# thermostatMechanicalSingleStage.net
KiCad netlist of a schematic drawn in EAGLE
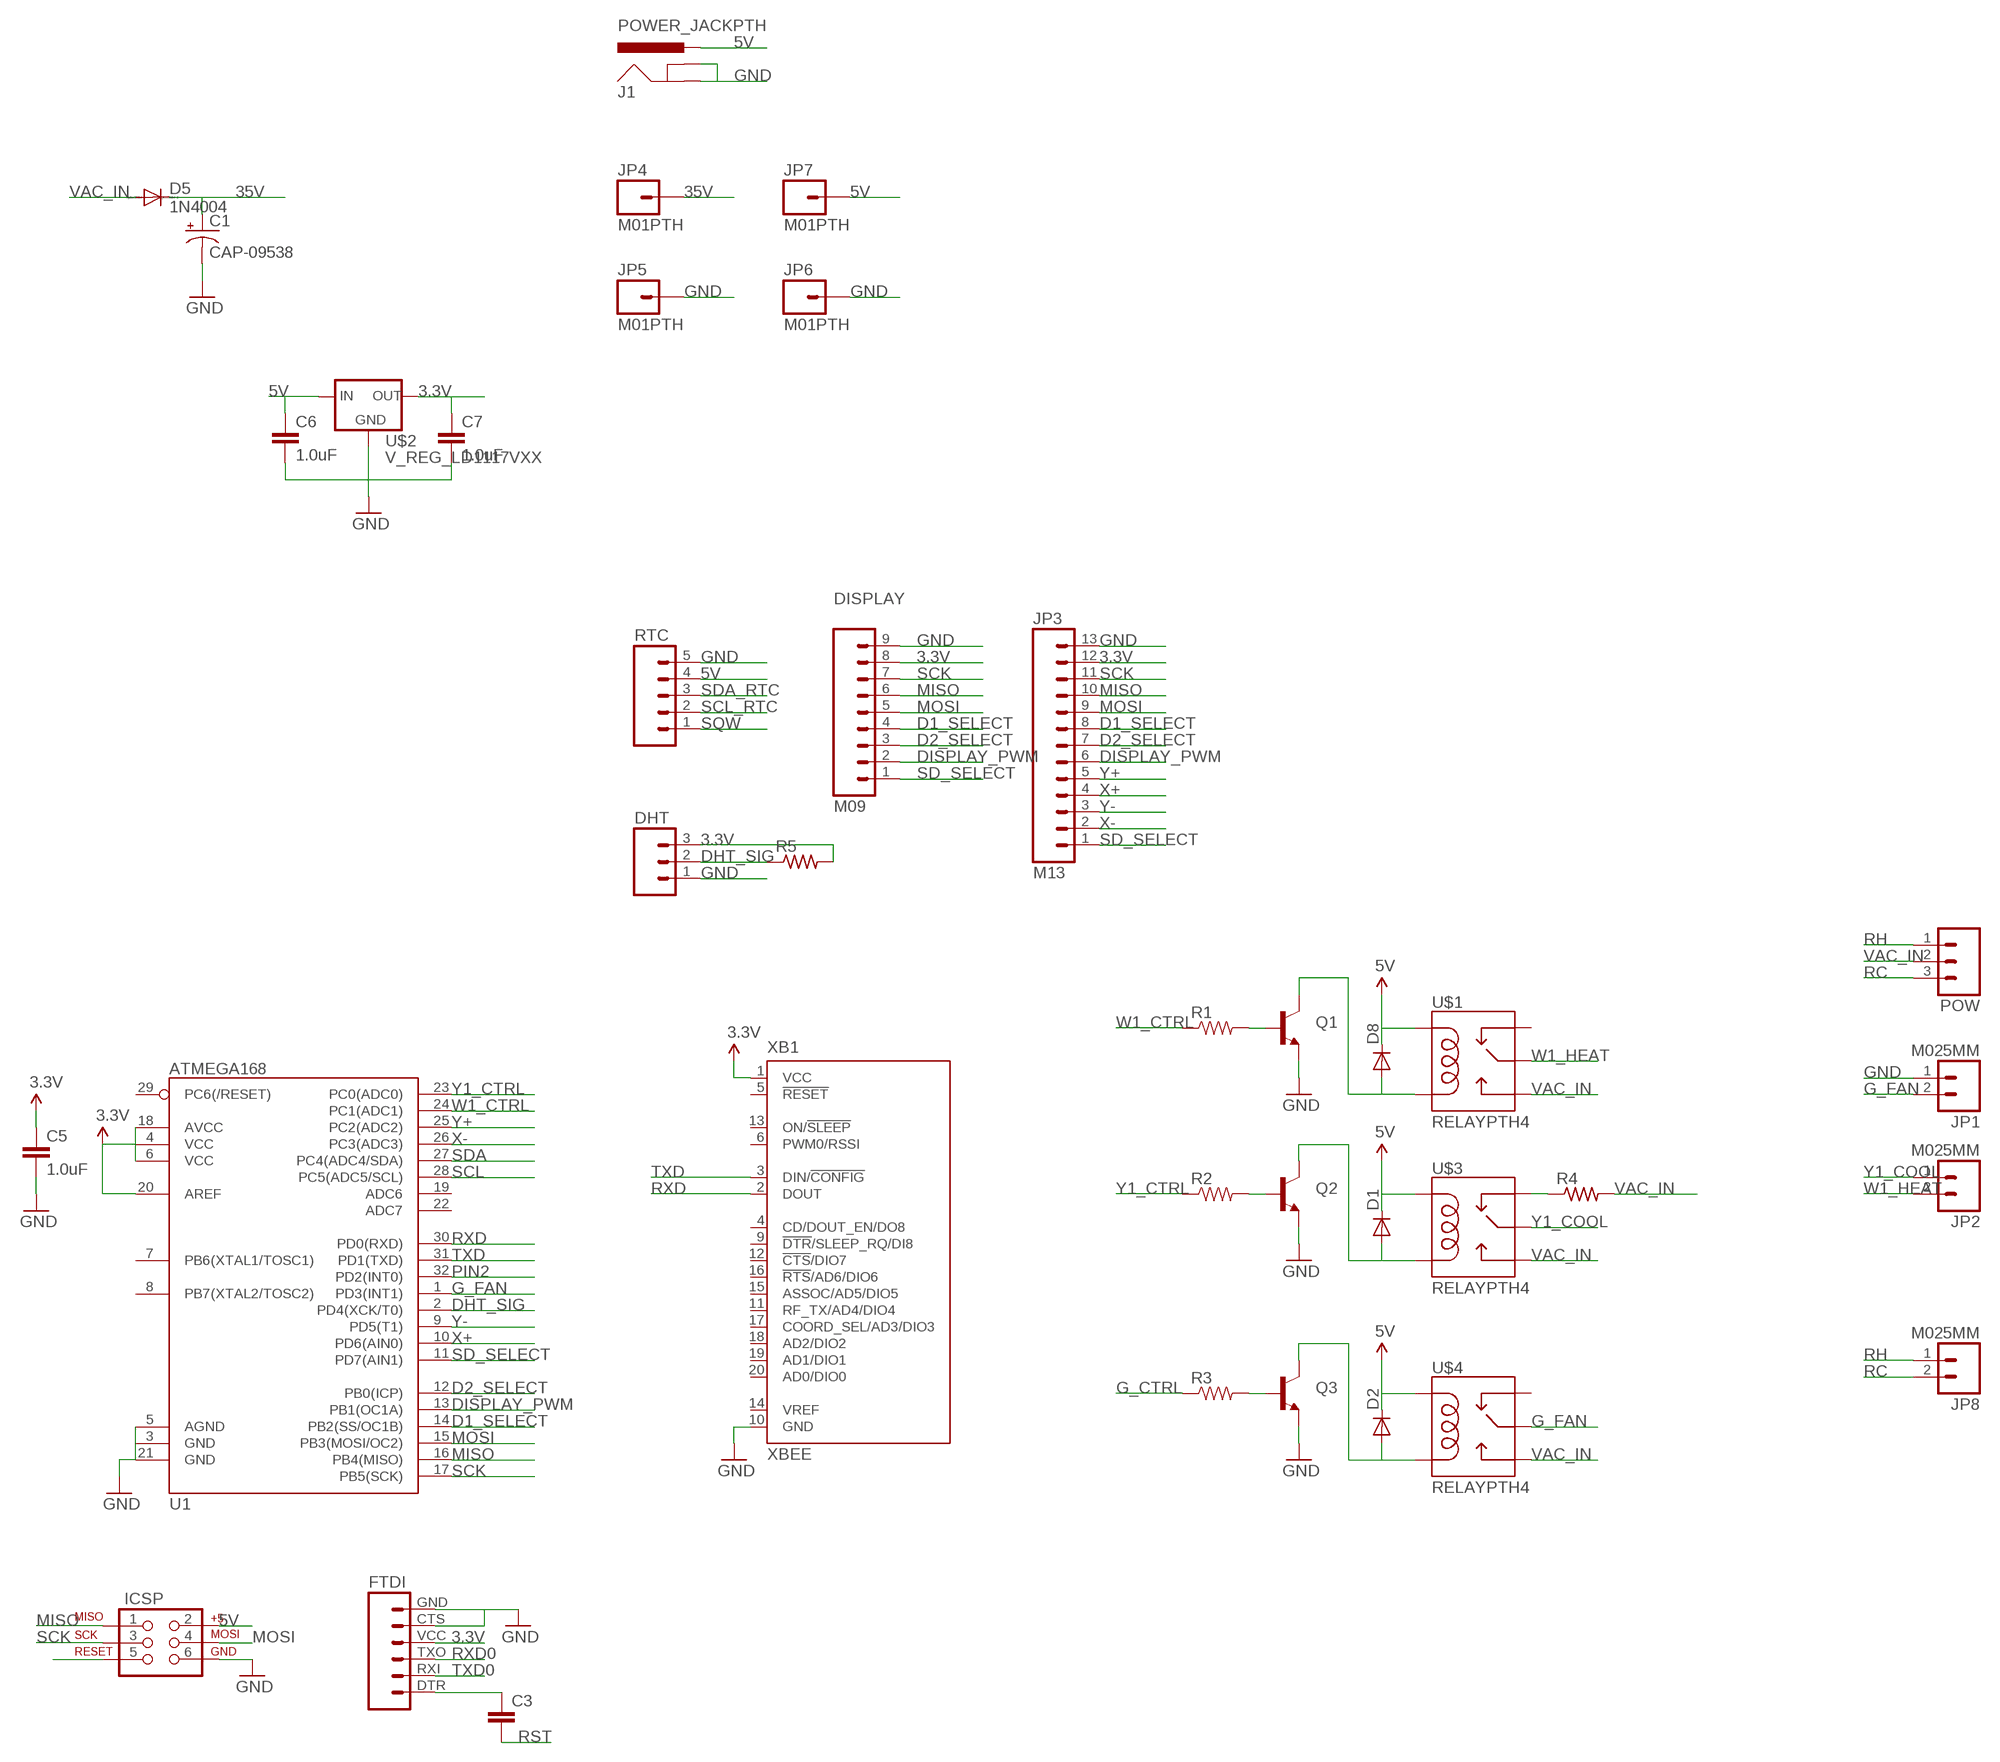
[diagram p0: schematic, sheet 1]

(export (version "E")
  (design (tool "Eeschema 10.0.6"))
  (components
    (comp (ref "C1")
      (value "CAP-09538")
      (footprint "eagle-import:CPOL-RADIAL-1000UF-25V")
      (libsource (lib "eagle-import") (part "1000UF-25V(PTH)"))
    )
    (comp (ref "C3")
      (value "CAP1206")
      (footprint "eagle-import:1206")
      (libsource (lib "eagle-import") (part "CAP1206"))
    )
    (comp (ref "C5")
      (value "1.0uF")
      (footprint "eagle-import:1206")
      (libsource (lib "eagle-import") (part "1.0UF50V10%(1206)"))
    )
    (comp (ref "C6")
      (value "1.0uF")
      (footprint "eagle-import:1206")
      (libsource (lib "eagle-import") (part "1.0UF50V10%(1206)"))
    )
    (comp (ref "C7")
      (value "1.0uF")
      (footprint "eagle-import:1206")
      (libsource (lib "eagle-import") (part "1.0UF50V10%(1206)"))
    )
    (comp (ref "D1")
      (value "DIODE1N4148")
      (footprint "eagle-import:DIODE-1N4148")
      (libsource (lib "eagle-import") (part "DIODE1N4148"))
    )
    (comp (ref "D2")
      (value "DIODE1N4148")
      (footprint "eagle-import:DIODE-1N4148")
      (libsource (lib "eagle-import") (part "DIODE1N4148"))
    )
    (comp (ref "D5")
      (value "1N4004")
      (footprint "eagle-import:DO41-10")
      (libsource (lib "eagle-import") (part "1N4004"))
    )
    (comp (ref "D8")
      (value "DIODE1N4148")
      (footprint "eagle-import:DIODE-1N4148")
      (libsource (lib "eagle-import") (part "DIODE1N4148"))
    )
    (comp (ref "DHT")
      (value "M03PTH")
      (footprint "eagle-import:1X03")
      (libsource (lib "eagle-import") (part "M03PTH"))
    )
    (comp (ref "DISPLAY")
      (value "M09")
      (footprint "eagle-import:1X09")
      (libsource (lib "eagle-import") (part "M09"))
    )
    (comp (ref "FTDI")
      (value "FTDI_BASICPTH")
      (footprint "eagle-import:FTDI_BASIC")
      (libsource (lib "eagle-import") (part "FTDI_BASICPTH"))
    )
    (comp (ref "ICSP")
      (value "AVR_SPI_PRG_6NS")
      (footprint "eagle-import:2X3-NS")
      (libsource (lib "eagle-import") (part "AVR_SPI_PRG_6NS"))
    )
    (comp (ref "J1")
      (value "POWER_JACKPTH")
      (footprint "eagle-import:POWER_JACK_PTH")
      (libsource (lib "eagle-import") (part "POWER_JACKPTH"))
    )
    (comp (ref "JP1")
      (value "M025MM")
      (footprint "eagle-import:SCREWTERMINAL-5MM-2")
      (libsource (lib "eagle-import") (part "M025MM"))
    )
    (comp (ref "JP2")
      (value "M025MM")
      (footprint "eagle-import:SCREWTERMINAL-5MM-2")
      (libsource (lib "eagle-import") (part "M025MM"))
    )
    (comp (ref "JP3")
      (value "M13")
      (footprint "eagle-import:1X13")
      (libsource (lib "eagle-import") (part "M13"))
    )
    (comp (ref "JP4")
      (value "M01PTH")
      (footprint "eagle-import:1X01")
      (libsource (lib "eagle-import") (part "M01PTH"))
    )
    (comp (ref "JP5")
      (value "M01PTH")
      (footprint "eagle-import:1X01")
      (libsource (lib "eagle-import") (part "M01PTH"))
    )
    (comp (ref "JP6")
      (value "M01PTH")
      (footprint "eagle-import:1X01")
      (libsource (lib "eagle-import") (part "M01PTH"))
    )
    (comp (ref "JP7")
      (value "M01PTH")
      (footprint "eagle-import:1X01")
      (libsource (lib "eagle-import") (part "M01PTH"))
    )
    (comp (ref "JP8")
      (value "M025MM")
      (footprint "eagle-import:SCREWTERMINAL-5MM-2")
      (libsource (lib "eagle-import") (part "M025MM"))
    )
    (comp (ref "POW")
      (value "M03PTH")
      (footprint "eagle-import:1X03")
      (libsource (lib "eagle-import") (part "M03PTH"))
    )
    (comp (ref "Q1")
      (value "TRANSISTOR_NPNSOT23")
      (footprint "eagle-import:SOT23")
      (libsource (lib "eagle-import") (part "TRANSISTOR_NPNSOT23"))
    )
    (comp (ref "Q2")
      (value "TRANSISTOR_NPNSOT23")
      (footprint "eagle-import:SOT23")
      (libsource (lib "eagle-import") (part "TRANSISTOR_NPNSOT23"))
    )
    (comp (ref "Q3")
      (value "TRANSISTOR_NPNSOT23")
      (footprint "eagle-import:SOT23")
      (libsource (lib "eagle-import") (part "TRANSISTOR_NPNSOT23"))
    )
    (comp (ref "R1")
      (value "RESISTOR1206")
      (footprint "eagle-import:1206")
      (libsource (lib "eagle-import") (part "RESISTOR1206"))
    )
    (comp (ref "R2")
      (value "RESISTOR1206")
      (footprint "eagle-import:1206")
      (libsource (lib "eagle-import") (part "RESISTOR1206"))
    )
    (comp (ref "R3")
      (value "RESISTOR1206")
      (footprint "eagle-import:1206")
      (libsource (lib "eagle-import") (part "RESISTOR1206"))
    )
    (comp (ref "R4")
      (value "R-US_0204/7")
      (footprint "eagle-import:0204_7")
      (libsource (lib "eagle-import") (part "rcl_R-US_0204/7"))
    )
    (comp (ref "R5")
      (value "R-US_M1206")
      (footprint "eagle-import:M1206")
      (libsource (lib "eagle-import") (part "R-US_M1206"))
    )
    (comp (ref "RTC")
      (value "M05PTH")
      (footprint "eagle-import:1X05")
      (libsource (lib "eagle-import") (part "M05PTH"))
    )
    (comp (ref "U$1")
      (value "RELAYPTH4")
      (footprint "eagle-import:RELAY-JZC")
      (libsource (lib "eagle-import") (part "RELAYPTH4"))
    )
    (comp (ref "U$2")
      (value "V_REG_LD1117VXX")
      (footprint "eagle-import:78XXL")
      (libsource (lib "eagle-import") (part "V_REG_LD1117VXX"))
    )
    (comp (ref "U$3")
      (value "RELAYPTH4")
      (footprint "eagle-import:RELAY-JZC")
      (libsource (lib "eagle-import") (part "RELAYPTH4"))
    )
    (comp (ref "U$4")
      (value "RELAYPTH4")
      (footprint "eagle-import:RELAY-JZC")
      (libsource (lib "eagle-import") (part "RELAYPTH4"))
    )
    (comp (ref "U1")
      (value "ATMEGA168")
      (footprint "eagle-import:TQFP32-08")
      (libsource (lib "eagle-import") (part "ATMEGA168"))
    )
    (comp (ref "XB1")
      (value "XBEE")
      (footprint "eagle-import:XBEE")
      (fields (field (name "MPN") "XBP24-Z7UIT-004"))
      (libsource (lib "eagle-import") (part "XBEE"))
    )
  )
  (nets
    (net (code "1") (name "/35V") (class "Default")
      (node (ref "C1") (pin "+") (pinfunction "+_+") (pintype "passive"))
      (node (ref "D5") (pin "C") (pinfunction "C_C") (pintype "passive"))
      (node (ref "JP4") (pin "1") (pinfunction "1_1") (pintype "passive"))
    )
    (net (code "2") (name "/D1_SELECT") (class "Default")
      (node (ref "DISPLAY") (pin "4") (pinfunction "4_4") (pintype "passive"))
      (node (ref "JP3") (pin "8") (pinfunction "8_8") (pintype "passive"))
      (node (ref "U1") (pin "14") (pinfunction "PB2(SS/OC1B)_14") (pintype "bidirectional"))
    )
    (net (code "3") (name "/D2_SELECT") (class "Default")
      (node (ref "DISPLAY") (pin "3") (pinfunction "3_3") (pintype "passive"))
      (node (ref "JP3") (pin "7") (pinfunction "7_7") (pintype "passive"))
      (node (ref "U1") (pin "12") (pinfunction "PB0(ICP)_12") (pintype "bidirectional"))
    )
    (net (code "4") (name "/DHT_SIG") (class "Default")
      (node (ref "DHT") (pin "2") (pinfunction "2_2") (pintype "passive"))
      (node (ref "R5") (pin "1") (pinfunction "1_1") (pintype "passive"))
      (node (ref "U1") (pin "2") (pinfunction "PD4(XCK/T0)_2") (pintype "bidirectional"))
    )
    (net (code "5") (name "/DISPLAY_PWM") (class "Default")
      (node (ref "DISPLAY") (pin "2") (pinfunction "2_2") (pintype "passive"))
      (node (ref "JP3") (pin "6") (pinfunction "6_6") (pintype "passive"))
      (node (ref "U1") (pin "13") (pinfunction "PB1(OC1A)_13") (pintype "bidirectional"))
    )
    (net (code "6") (name "/G_CTRL") (class "Default")
      (node (ref "R3") (pin "1") (pinfunction "1_1") (pintype "passive"))
    )
    (net (code "7") (name "/G_FAN") (class "Default")
      (node (ref "JP1") (pin "2") (pinfunction "2_2") (pintype "passive"))
      (node (ref "U$4") (pin "4") (pinfunction "MAIN_4") (pintype "bidirectional"))
      (node (ref "U1") (pin "1") (pinfunction "PD3(INT1)_1") (pintype "bidirectional"))
    )
    (net (code "8") (name "/MISO") (class "Default")
      (node (ref "DISPLAY") (pin "6") (pinfunction "6_6") (pintype "passive"))
      (node (ref "ICSP") (pin "1") (pinfunction "1_1") (pintype "passive"))
      (node (ref "JP3") (pin "10") (pinfunction "10_10") (pintype "passive"))
      (node (ref "U1") (pin "16") (pinfunction "PB4(MISO)_16") (pintype "bidirectional"))
    )
    (net (code "9") (name "/MOSI") (class "Default")
      (node (ref "DISPLAY") (pin "5") (pinfunction "5_5") (pintype "passive"))
      (node (ref "ICSP") (pin "4") (pinfunction "4_4") (pintype "passive"))
      (node (ref "JP3") (pin "9") (pinfunction "9_9") (pintype "passive"))
      (node (ref "U1") (pin "15") (pinfunction "PB3(MOSI/OC2)_15") (pintype "bidirectional"))
    )
    (net (code "10") (name "/PIN2") (class "Default")
      (node (ref "U1") (pin "32") (pinfunction "PD2(INT0)_32") (pintype "bidirectional"))
    )
    (net (code "11") (name "/RC") (class "Default")
      (node (ref "JP8") (pin "2") (pinfunction "2_2") (pintype "passive"))
      (node (ref "POW") (pin "3") (pinfunction "3_3") (pintype "passive"))
    )
    (net (code "12") (name "/RH") (class "Default")
      (node (ref "JP8") (pin "1") (pinfunction "1_1") (pintype "passive"))
      (node (ref "POW") (pin "1") (pinfunction "1_1") (pintype "passive"))
    )
    (net (code "13") (name "/RST") (class "Default")
      (node (ref "C3") (pin "2") (pinfunction "2_2") (pintype "passive"))
      (node (ref "ICSP") (pin "5") (pinfunction "5_5") (pintype "passive"))
    )
    (net (code "14") (name "/RXD") (class "Default")
      (node (ref "U1") (pin "30") (pinfunction "PD0(RXD)_30") (pintype "bidirectional"))
      (node (ref "XB1") (pin "2") (pinfunction "DOUT_2") (pintype "output"))
    )
    (net (code "15") (name "/RXD0") (class "Default")
      (node (ref "FTDI") (pin "TXO") (pinfunction "3_TXO") (pintype "passive"))
    )
    (net (code "16") (name "/SCK") (class "Default")
      (node (ref "DISPLAY") (pin "7") (pinfunction "7_7") (pintype "passive"))
      (node (ref "ICSP") (pin "3") (pinfunction "3_3") (pintype "passive"))
      (node (ref "JP3") (pin "11") (pinfunction "11_11") (pintype "passive"))
      (node (ref "U1") (pin "17") (pinfunction "PB5(SCK)_17") (pintype "bidirectional"))
    )
    (net (code "17") (name "/SCL") (class "Default")
      (node (ref "U1") (pin "28") (pinfunction "PC5(ADC5/SCL)_28") (pintype "bidirectional"))
    )
    (net (code "18") (name "/SCL_RTC") (class "Default")
      (node (ref "RTC") (pin "2") (pinfunction "2_2") (pintype "passive"))
    )
    (net (code "19") (name "/SDA") (class "Default")
      (node (ref "U1") (pin "27") (pinfunction "PC4(ADC4/SDA)_27") (pintype "bidirectional"))
    )
    (net (code "20") (name "/SDA_RTC") (class "Default")
      (node (ref "RTC") (pin "3") (pinfunction "3_3") (pintype "passive"))
    )
    (net (code "21") (name "/SD_SELECT") (class "Default")
      (node (ref "DISPLAY") (pin "1") (pinfunction "1_1") (pintype "passive"))
      (node (ref "JP3") (pin "1") (pinfunction "1_1") (pintype "passive"))
      (node (ref "U1") (pin "11") (pinfunction "PD7(AIN1)_11") (pintype "bidirectional"))
    )
    (net (code "22") (name "/SQW") (class "Default")
      (node (ref "RTC") (pin "1") (pinfunction "1_1") (pintype "passive"))
    )
    (net (code "23") (name "/TXD") (class "Default")
      (node (ref "U1") (pin "31") (pinfunction "PD1(TXD)_31") (pintype "bidirectional"))
      (node (ref "XB1") (pin "3") (pinfunction "DIN/~{CONFIG}_3") (pintype "input"))
    )
    (net (code "24") (name "/TXD0") (class "Default")
      (node (ref "FTDI") (pin "RXI") (pinfunction "2_RXI") (pintype "passive"))
    )
    (net (code "25") (name "/VAC_IN") (class "Default")
      (node (ref "D5") (pin "A") (pinfunction "A_A") (pintype "passive"))
      (node (ref "POW") (pin "2") (pinfunction "2_2") (pintype "passive"))
      (node (ref "R4") (pin "2") (pinfunction "2_2") (pintype "passive"))
      (node (ref "U$1") (pin "3") (pinfunction "NO_3") (pintype "bidirectional"))
      (node (ref "U$3") (pin "3") (pinfunction "NO_3") (pintype "bidirectional"))
      (node (ref "U$4") (pin "3") (pinfunction "NO_3") (pintype "bidirectional"))
    )
    (net (code "26") (name "/W1_CTRL") (class "Default")
      (node (ref "R1") (pin "1") (pinfunction "1_1") (pintype "passive"))
      (node (ref "U1") (pin "24") (pinfunction "PC1(ADC1)_24") (pintype "bidirectional"))
    )
    (net (code "27") (name "/W1_HEAT") (class "Default")
      (node (ref "JP2") (pin "2") (pinfunction "2_2") (pintype "passive"))
      (node (ref "U$1") (pin "4") (pinfunction "MAIN_4") (pintype "bidirectional"))
    )
    (net (code "28") (name "/X+") (class "Default")
      (node (ref "JP3") (pin "4") (pinfunction "4_4") (pintype "passive"))
      (node (ref "U1") (pin "10") (pinfunction "PD6(AIN0)_10") (pintype "bidirectional"))
    )
    (net (code "29") (name "/X-") (class "Default")
      (node (ref "JP3") (pin "2") (pinfunction "2_2") (pintype "passive"))
      (node (ref "U1") (pin "26") (pinfunction "PC3(ADC3)_26") (pintype "bidirectional"))
    )
    (net (code "30") (name "/Y+") (class "Default")
      (node (ref "JP3") (pin "5") (pinfunction "5_5") (pintype "passive"))
      (node (ref "U1") (pin "25") (pinfunction "PC2(ADC2)_25") (pintype "bidirectional"))
    )
    (net (code "31") (name "/Y-") (class "Default")
      (node (ref "JP3") (pin "3") (pinfunction "3_3") (pintype "passive"))
      (node (ref "U1") (pin "9") (pinfunction "PD5(T1)_9") (pintype "bidirectional"))
    )
    (net (code "32") (name "/Y1_COOL") (class "Default")
      (node (ref "JP2") (pin "1") (pinfunction "1_1") (pintype "passive"))
      (node (ref "U$3") (pin "4") (pinfunction "MAIN_4") (pintype "bidirectional"))
    )
    (net (code "33") (name "/Y1_CTRL") (class "Default")
      (node (ref "R2") (pin "1") (pinfunction "1_1") (pintype "passive"))
      (node (ref "U1") (pin "23") (pinfunction "PC0(ADC0)_23") (pintype "bidirectional"))
    )
    (net (code "34") (name "3.3V") (class "Default")
      (node (ref "C5") (pin "1") (pinfunction "1_1") (pintype "passive"))
      (node (ref "C7") (pin "1") (pinfunction "1_1") (pintype "passive"))
      (node (ref "DHT") (pin "3") (pinfunction "3_3") (pintype "passive"))
      (node (ref "DISPLAY") (pin "8") (pinfunction "8_8") (pintype "passive"))
      (node (ref "FTDI") (pin "VCC") (pinfunction "4_VCC") (pintype "passive"))
      (node (ref "JP3") (pin "12") (pinfunction "12_12") (pintype "passive"))
      (node (ref "R5") (pin "2") (pinfunction "2_2") (pintype "passive"))
      (node (ref "U$2") (pin "GND") (pinfunction "OUT_GND") (pintype "output"))
      (node (ref "U1") (pin "18") (pinfunction "AVCC_18") (pintype "bidirectional"))
      (node (ref "U1") (pin "20") (pinfunction "AREF_20") (pintype "bidirectional"))
      (node (ref "U1") (pin "4") (pinfunction "VCC_4") (pintype "bidirectional"))
      (node (ref "U1") (pin "6") (pinfunction "VCC_6") (pintype "bidirectional"))
      (node (ref "XB1") (pin "1") (pinfunction "VCC_1") (pintype "power_in"))
    )
    (net (code "35") (name "5V") (class "Default")
      (node (ref "C6") (pin "1") (pinfunction "1_1") (pintype "passive"))
      (node (ref "D1") (pin "C") (pinfunction "C_C") (pintype "passive"))
      (node (ref "D2") (pin "C") (pinfunction "C_C") (pintype "passive"))
      (node (ref "D8") (pin "C") (pinfunction "C_C") (pintype "passive"))
      (node (ref "ICSP") (pin "2") (pinfunction "2_2") (pintype "passive"))
      (node (ref "J1") (pin "PWR") (pinfunction "PWR_PWR") (pintype "bidirectional"))
      (node (ref "JP7") (pin "1") (pinfunction "1_1") (pintype "passive"))
      (node (ref "RTC") (pin "4") (pinfunction "4_4") (pintype "passive"))
      (node (ref "U$1") (pin "5") (pinfunction "COIL1_5") (pintype "bidirectional"))
      (node (ref "U$2") (pin "OUT") (pinfunction "IN_OUT") (pintype "input"))
      (node (ref "U$3") (pin "5") (pinfunction "COIL1_5") (pintype "bidirectional"))
      (node (ref "U$4") (pin "5") (pinfunction "COIL1_5") (pintype "bidirectional"))
    )
    (net (code "36") (name "GND") (class "Default")
      (node (ref "C1") (pin "-") (pinfunction "-_-") (pintype "passive"))
      (node (ref "C5") (pin "2") (pinfunction "2_2") (pintype "passive"))
      (node (ref "C6") (pin "2") (pinfunction "2_2") (pintype "passive"))
      (node (ref "C7") (pin "2") (pinfunction "2_2") (pintype "passive"))
      (node (ref "DHT") (pin "1") (pinfunction "1_1") (pintype "passive"))
      (node (ref "DISPLAY") (pin "9") (pinfunction "9_9") (pintype "passive"))
      (node (ref "FTDI") (pin "CTS") (pinfunction "5_CTS") (pintype "passive"))
      (node (ref "FTDI") (pin "GND") (pinfunction "6_GND") (pintype "passive"))
      (node (ref "ICSP") (pin "6") (pinfunction "6_6") (pintype "passive"))
      (node (ref "J1") (pin "GND") (pinfunction "GND_GND") (pintype "bidirectional"))
      (node (ref "J1") (pin "GNDBREAK") (pinfunction "GNDBREAK_GNDBREAK") (pintype "bidirectional"))
      (node (ref "JP1") (pin "1") (pinfunction "1_1") (pintype "passive"))
      (node (ref "JP3") (pin "13") (pinfunction "13_13") (pintype "passive"))
      (node (ref "JP5") (pin "1") (pinfunction "1_1") (pintype "passive"))
      (node (ref "JP6") (pin "1") (pinfunction "1_1") (pintype "passive"))
      (node (ref "Q1") (pin "2") (pinfunction "E_2") (pintype "passive"))
      (node (ref "Q2") (pin "2") (pinfunction "E_2") (pintype "passive"))
      (node (ref "Q3") (pin "2") (pinfunction "E_2") (pintype "passive"))
      (node (ref "RTC") (pin "5") (pinfunction "5_5") (pintype "passive"))
      (node (ref "U$2") (pin "IN") (pinfunction "GND_IN") (pintype "input"))
      (node (ref "U1") (pin "21") (pinfunction "GND_21") (pintype "bidirectional"))
      (node (ref "U1") (pin "3") (pinfunction "GND_3") (pintype "bidirectional"))
      (node (ref "U1") (pin "5") (pinfunction "AGND_5") (pintype "bidirectional"))
      (node (ref "XB1") (pin "10") (pinfunction "GND_10") (pintype "power_in"))
    )
    (net (code "37") (name "Net-(FTDI-1)") (class "Default")
      (node (ref "C3") (pin "1") (pinfunction "1_1") (pintype "passive"))
      (node (ref "FTDI") (pin "DTR") (pinfunction "1_DTR") (pintype "passive"))
    )
    (net (code "38") (name "Net-(Q1-B)") (class "Default")
      (node (ref "Q1") (pin "1") (pinfunction "B_1") (pintype "passive"))
      (node (ref "R1") (pin "2") (pinfunction "2_2") (pintype "passive"))
    )
    (net (code "39") (name "Net-(Q1-C)") (class "Default")
      (node (ref "D8") (pin "A") (pinfunction "A_A") (pintype "passive"))
      (node (ref "Q1") (pin "3") (pinfunction "C_3") (pintype "passive"))
      (node (ref "U$1") (pin "1") (pinfunction "COIL2_1") (pintype "bidirectional"))
    )
    (net (code "40") (name "Net-(Q2-B)") (class "Default")
      (node (ref "Q2") (pin "1") (pinfunction "B_1") (pintype "passive"))
      (node (ref "R2") (pin "2") (pinfunction "2_2") (pintype "passive"))
    )
    (net (code "41") (name "Net-(Q2-C)") (class "Default")
      (node (ref "D1") (pin "A") (pinfunction "A_A") (pintype "passive"))
      (node (ref "Q2") (pin "3") (pinfunction "C_3") (pintype "passive"))
      (node (ref "U$3") (pin "1") (pinfunction "COIL2_1") (pintype "bidirectional"))
    )
    (net (code "42") (name "Net-(Q3-B)") (class "Default")
      (node (ref "Q3") (pin "1") (pinfunction "B_1") (pintype "passive"))
      (node (ref "R3") (pin "2") (pinfunction "2_2") (pintype "passive"))
    )
    (net (code "43") (name "Net-(Q3-C)") (class "Default")
      (node (ref "D2") (pin "A") (pinfunction "A_A") (pintype "passive"))
      (node (ref "Q3") (pin "3") (pinfunction "C_3") (pintype "passive"))
      (node (ref "U$4") (pin "1") (pinfunction "COIL2_1") (pintype "bidirectional"))
    )
    (net (code "44") (name "Net-(U$3-NC)") (class "Default")
      (node (ref "R4") (pin "1") (pinfunction "1_1") (pintype "passive"))
      (node (ref "U$3") (pin "2") (pinfunction "NC_2") (pintype "bidirectional"))
    )
    (net (code "45") (name "unconnected-(U$1-NC-Pad2)") (class "Default")
      (node (ref "U$1") (pin "2") (pinfunction "NC_2") (pintype "bidirectional"))
    )
    (net (code "46") (name "unconnected-(U$4-NC-Pad2)") (class "Default")
      (node (ref "U$4") (pin "2") (pinfunction "NC_2") (pintype "bidirectional"))
    )
    (net (code "47") (name "unconnected-(U1-ADC6-Pad19)") (class "Default")
      (node (ref "U1") (pin "19") (pinfunction "ADC6_19") (pintype "bidirectional"))
    )
    (net (code "48") (name "unconnected-(U1-ADC7-Pad22)") (class "Default")
      (node (ref "U1") (pin "22") (pinfunction "ADC7_22") (pintype "bidirectional"))
    )
    (net (code "49") (name "unconnected-(U1-PB6(XTAL1{slash}TOSC1)-Pad7)") (class "Default")
      (node (ref "U1") (pin "7") (pinfunction "PB6(XTAL1/TOSC1)_7") (pintype "bidirectional"))
    )
    (net (code "50") (name "unconnected-(U1-PB7(XTAL2{slash}TOSC2)-Pad8)") (class "Default")
      (node (ref "U1") (pin "8") (pinfunction "PB7(XTAL2/TOSC2)_8") (pintype "bidirectional"))
    )
    (net (code "51") (name "unconnected-(U1-PC6({slash}RESET)-Pad29)") (class "Default")
      (node (ref "U1") (pin "29") (pinfunction "PC6(/RESET)_29") (pintype "bidirectional"))
    )
    (net (code "52") (name "unconnected-(XB1-AD0{slash}DIO0-Pad20)") (class "Default")
      (node (ref "XB1") (pin "20") (pinfunction "AD0/DIO0_20") (pintype "bidirectional"))
    )
    (net (code "53") (name "unconnected-(XB1-AD1{slash}DIO1-Pad19)") (class "Default")
      (node (ref "XB1") (pin "19") (pinfunction "AD1/DIO1_19") (pintype "bidirectional"))
    )
    (net (code "54") (name "unconnected-(XB1-AD2{slash}DIO2-Pad18)") (class "Default")
      (node (ref "XB1") (pin "18") (pinfunction "AD2/DIO2_18") (pintype "bidirectional"))
    )
    (net (code "55") (name "unconnected-(XB1-ASSOC{slash}AD5{slash}DIO5-Pad15)") (class "Default")
      (node (ref "XB1") (pin "15") (pinfunction "ASSOC/AD5/DIO5_15") (pintype "bidirectional"))
    )
    (net (code "56") (name "unconnected-(XB1-CD{slash}DOUT_EN{slash}DO8-Pad4)") (class "Default")
      (node (ref "XB1") (pin "4") (pinfunction "CD/DOUT_EN/DO8_4") (pintype "output"))
    )
    (net (code "57") (name "unconnected-(XB1-COORD_SEL{slash}AD3{slash}DIO3-Pad17)") (class "Default")
      (node (ref "XB1") (pin "17") (pinfunction "COORD_SEL/AD3/DIO3_17") (pintype "bidirectional"))
    )
    (net (code "58") (name "unconnected-(XB1-ON{slash}~{SLEEP}-Pad13)") (class "Default")
      (node (ref "XB1") (pin "13") (pinfunction "ON/~{SLEEP}_13") (pintype "output"))
    )
    (net (code "59") (name "unconnected-(XB1-PWM0{slash}RSSI-Pad6)") (class "Default")
      (node (ref "XB1") (pin "6") (pinfunction "PWM0/RSSI_6") (pintype "output"))
    )
    (net (code "60") (name "unconnected-(XB1-RF_TX{slash}AD4{slash}DIO4-Pad11)") (class "Default")
      (node (ref "XB1") (pin "11") (pinfunction "RF_TX/AD4/DIO4_11") (pintype "bidirectional"))
    )
    (net (code "61") (name "unconnected-(XB1-VREF-Pad14)") (class "Default")
      (node (ref "XB1") (pin "14") (pinfunction "VREF_14") (pintype "input"))
    )
    (net (code "62") (name "unconnected-(XB1-~{CTS}{slash}DIO7-Pad12)") (class "Default")
      (node (ref "XB1") (pin "12") (pinfunction "~{CTS}/DIO7_12") (pintype "bidirectional"))
    )
    (net (code "63") (name "unconnected-(XB1-~{DTR}{slash}SLEEP_RQ{slash}DI8-Pad9)") (class "Default")
      (node (ref "XB1") (pin "9") (pinfunction "~{DTR}/SLEEP_RQ/DI8_9") (pintype "bidirectional"))
    )
    (net (code "64") (name "unconnected-(XB1-~{RESET}-Pad5)") (class "Default")
      (node (ref "XB1") (pin "5") (pinfunction "~{RESET}_5") (pintype "input"))
    )
    (net (code "65") (name "unconnected-(XB1-~{RTS}{slash}AD6{slash}DIO6-Pad16)") (class "Default")
      (node (ref "XB1") (pin "16") (pinfunction "~{RTS}/AD6/DIO6_16") (pintype "bidirectional"))
    )
  )
)
